# MRCS-Showcase-Miniature-Signal-Adapter.net
KiCad netlist of a schematic drawn in EAGLE
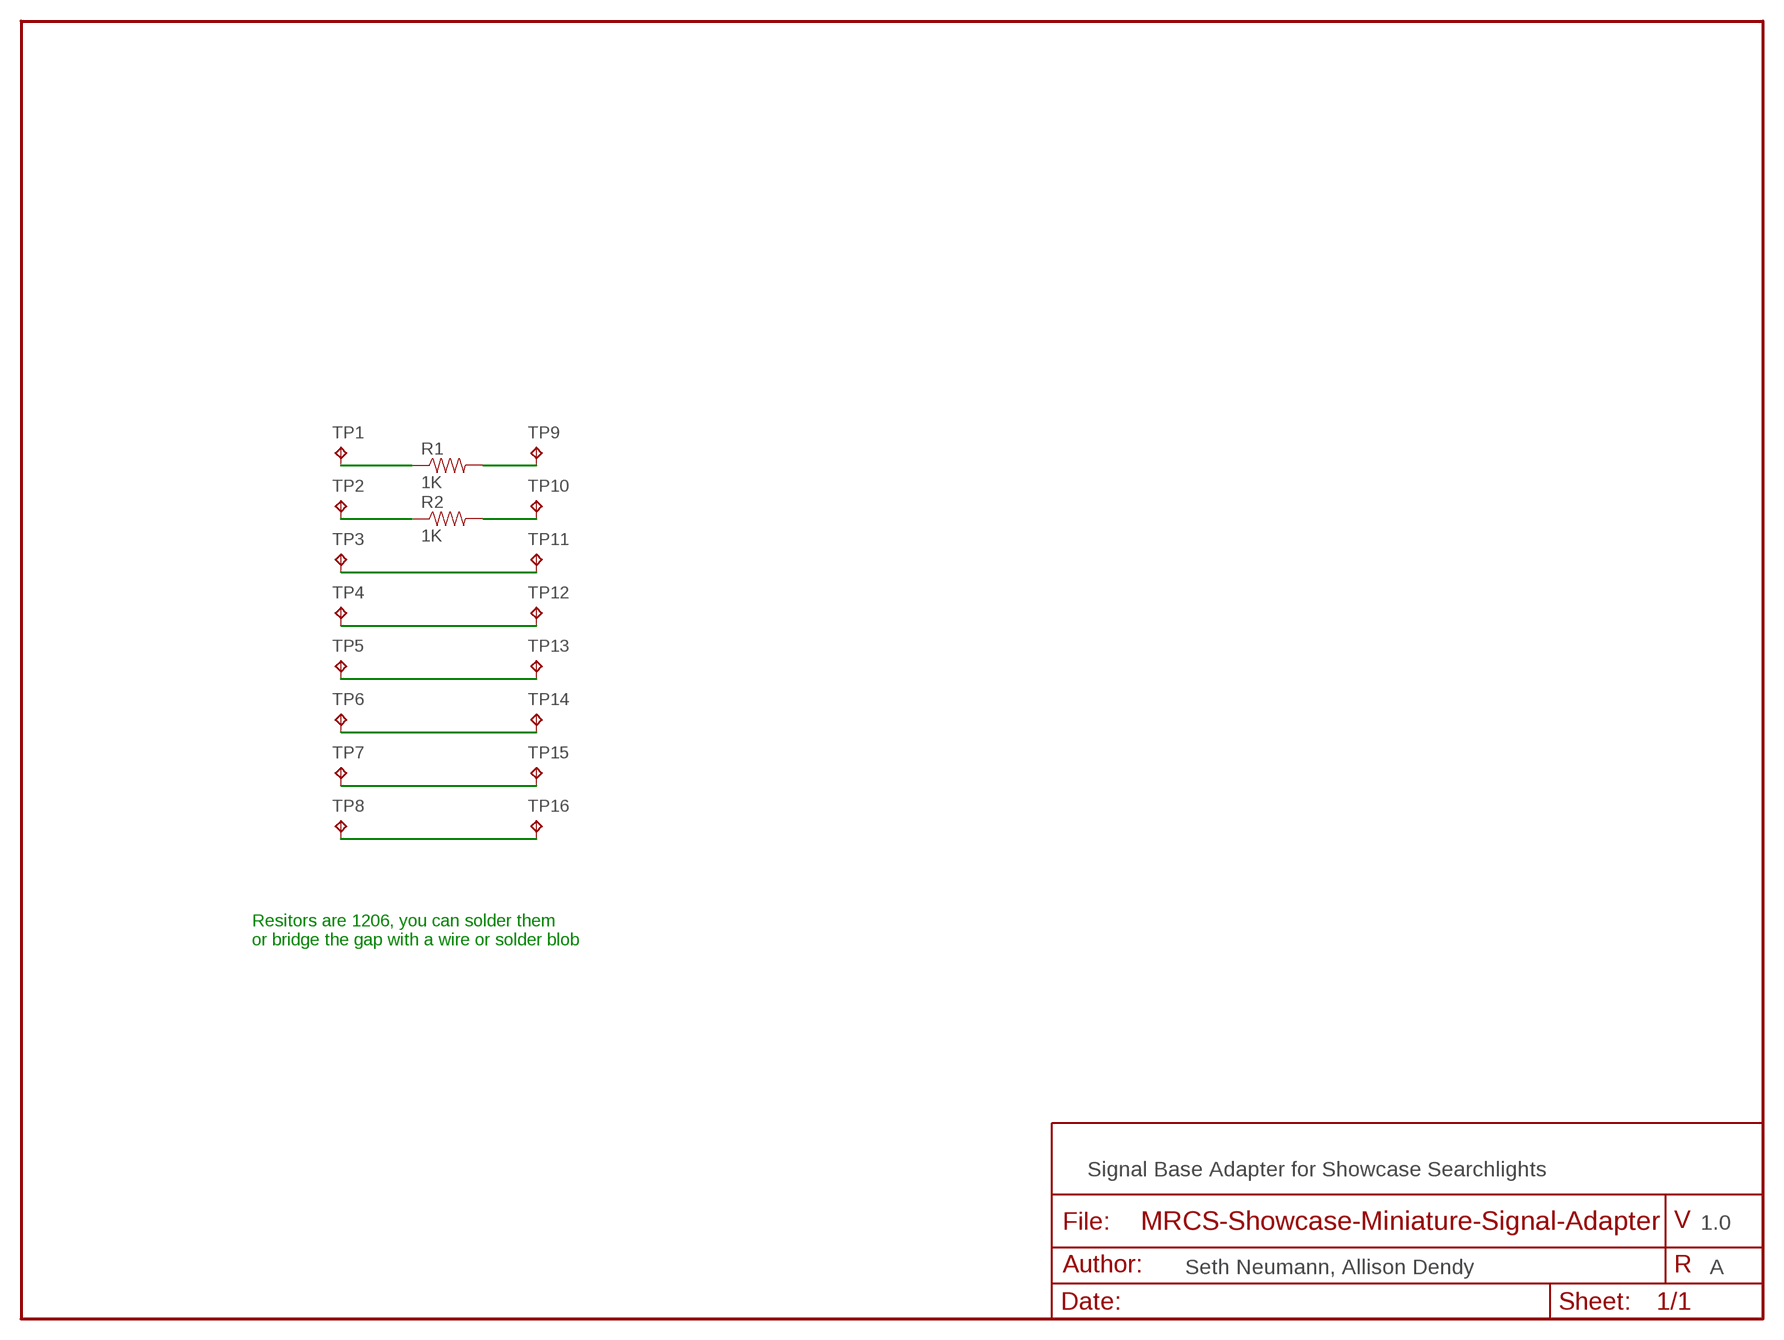
[diagram p0: schematic, sheet 1]

(export (version "E")
  (design (tool "Eeschema 10.0.6"))
  (components
    (comp (ref "R1")
      (value "1K")
      (footprint "eagle-import:1206-RES")
      (libsource (lib "eagle-import") (part "R1206"))
    )
    (comp (ref "R2")
      (value "1K")
      (footprint "eagle-import:1206-RES")
      (libsource (lib "eagle-import") (part "R1206"))
    )
    (comp (ref "TP1")
      (value "TP")
      (footprint "eagle-import:P1-06")
      (libsource (lib "eagle-import") (part "TP"))
    )
    (comp (ref "TP2")
      (value "TP")
      (footprint "eagle-import:P1-06")
      (libsource (lib "eagle-import") (part "TP"))
    )
    (comp (ref "TP3")
      (value "TP")
      (footprint "eagle-import:P1-06")
      (libsource (lib "eagle-import") (part "TP"))
    )
    (comp (ref "TP4")
      (value "TP")
      (footprint "eagle-import:P1-06")
      (libsource (lib "eagle-import") (part "TP"))
    )
    (comp (ref "TP5")
      (value "TP")
      (footprint "eagle-import:P1-06")
      (libsource (lib "eagle-import") (part "TP"))
    )
    (comp (ref "TP6")
      (value "TP")
      (footprint "eagle-import:P1-06")
      (libsource (lib "eagle-import") (part "TP"))
    )
    (comp (ref "TP7")
      (value "TP")
      (footprint "eagle-import:P1-06")
      (libsource (lib "eagle-import") (part "TP"))
    )
    (comp (ref "TP8")
      (value "TP")
      (footprint "eagle-import:P1-06")
      (libsource (lib "eagle-import") (part "TP"))
    )
    (comp (ref "TP9")
      (value "TP")
      (footprint "eagle-import:P1-06")
      (libsource (lib "eagle-import") (part "TP"))
    )
    (comp (ref "TP10")
      (value "TP")
      (footprint "eagle-import:P1-06")
      (libsource (lib "eagle-import") (part "TP"))
    )
    (comp (ref "TP11")
      (value "TP")
      (footprint "eagle-import:P1-06")
      (libsource (lib "eagle-import") (part "TP"))
    )
    (comp (ref "TP12")
      (value "TP")
      (footprint "eagle-import:P1-06")
      (libsource (lib "eagle-import") (part "TP"))
    )
    (comp (ref "TP13")
      (value "TP")
      (footprint "eagle-import:P1-06")
      (libsource (lib "eagle-import") (part "TP"))
    )
    (comp (ref "TP14")
      (value "TP")
      (footprint "eagle-import:P1-06")
      (libsource (lib "eagle-import") (part "TP"))
    )
    (comp (ref "TP15")
      (value "TP")
      (footprint "eagle-import:P1-06")
      (libsource (lib "eagle-import") (part "TP"))
    )
    (comp (ref "TP16")
      (value "TP")
      (footprint "eagle-import:P1-06")
      (libsource (lib "eagle-import") (part "TP"))
    )
  )
  (nets
    (net (code "1") (name "Net-(TP1-TP)") (class "Default")
      (node (ref "R1") (pin "1") (pinfunction "1_1") (pintype "passive"))
      (node (ref "TP1") (pin "P$1") (pinfunction "TP_P$1") (pintype "input"))
    )
    (net (code "2") (name "Net-(TP2-TP)") (class "Default")
      (node (ref "R2") (pin "1") (pinfunction "1_1") (pintype "passive"))
      (node (ref "TP2") (pin "P$1") (pinfunction "TP_P$1") (pintype "input"))
    )
    (net (code "3") (name "Net-(TP9-TP)") (class "Default")
      (node (ref "R1") (pin "2") (pinfunction "2_2") (pintype "passive"))
      (node (ref "TP9") (pin "P$1") (pinfunction "TP_P$1") (pintype "input"))
    )
    (net (code "4") (name "Net-(TP10-TP)") (class "Default")
      (node (ref "R2") (pin "2") (pinfunction "2_2") (pintype "passive"))
      (node (ref "TP10") (pin "P$1") (pinfunction "TP_P$1") (pintype "input"))
    )
    (net (code "5") (name "Net-(TP11-TP)") (class "Default")
      (node (ref "TP11") (pin "P$1") (pinfunction "TP_P$1") (pintype "input"))
      (node (ref "TP3") (pin "P$1") (pinfunction "TP_P$1") (pintype "input"))
    )
    (net (code "6") (name "Net-(TP12-TP)") (class "Default")
      (node (ref "TP12") (pin "P$1") (pinfunction "TP_P$1") (pintype "input"))
      (node (ref "TP4") (pin "P$1") (pinfunction "TP_P$1") (pintype "input"))
    )
    (net (code "7") (name "Net-(TP13-TP)") (class "Default")
      (node (ref "TP13") (pin "P$1") (pinfunction "TP_P$1") (pintype "input"))
      (node (ref "TP5") (pin "P$1") (pinfunction "TP_P$1") (pintype "input"))
    )
    (net (code "8") (name "Net-(TP14-TP)") (class "Default")
      (node (ref "TP14") (pin "P$1") (pinfunction "TP_P$1") (pintype "input"))
      (node (ref "TP6") (pin "P$1") (pinfunction "TP_P$1") (pintype "input"))
    )
    (net (code "9") (name "Net-(TP15-TP)") (class "Default")
      (node (ref "TP15") (pin "P$1") (pinfunction "TP_P$1") (pintype "input"))
      (node (ref "TP7") (pin "P$1") (pinfunction "TP_P$1") (pintype "input"))
    )
    (net (code "10") (name "Net-(TP16-TP)") (class "Default")
      (node (ref "TP16") (pin "P$1") (pinfunction "TP_P$1") (pintype "input"))
      (node (ref "TP8") (pin "P$1") (pinfunction "TP_P$1") (pintype "input"))
    )
  )
)
